# sane_serial.net
KiCad netlist of a schematic drawn in EAGLE
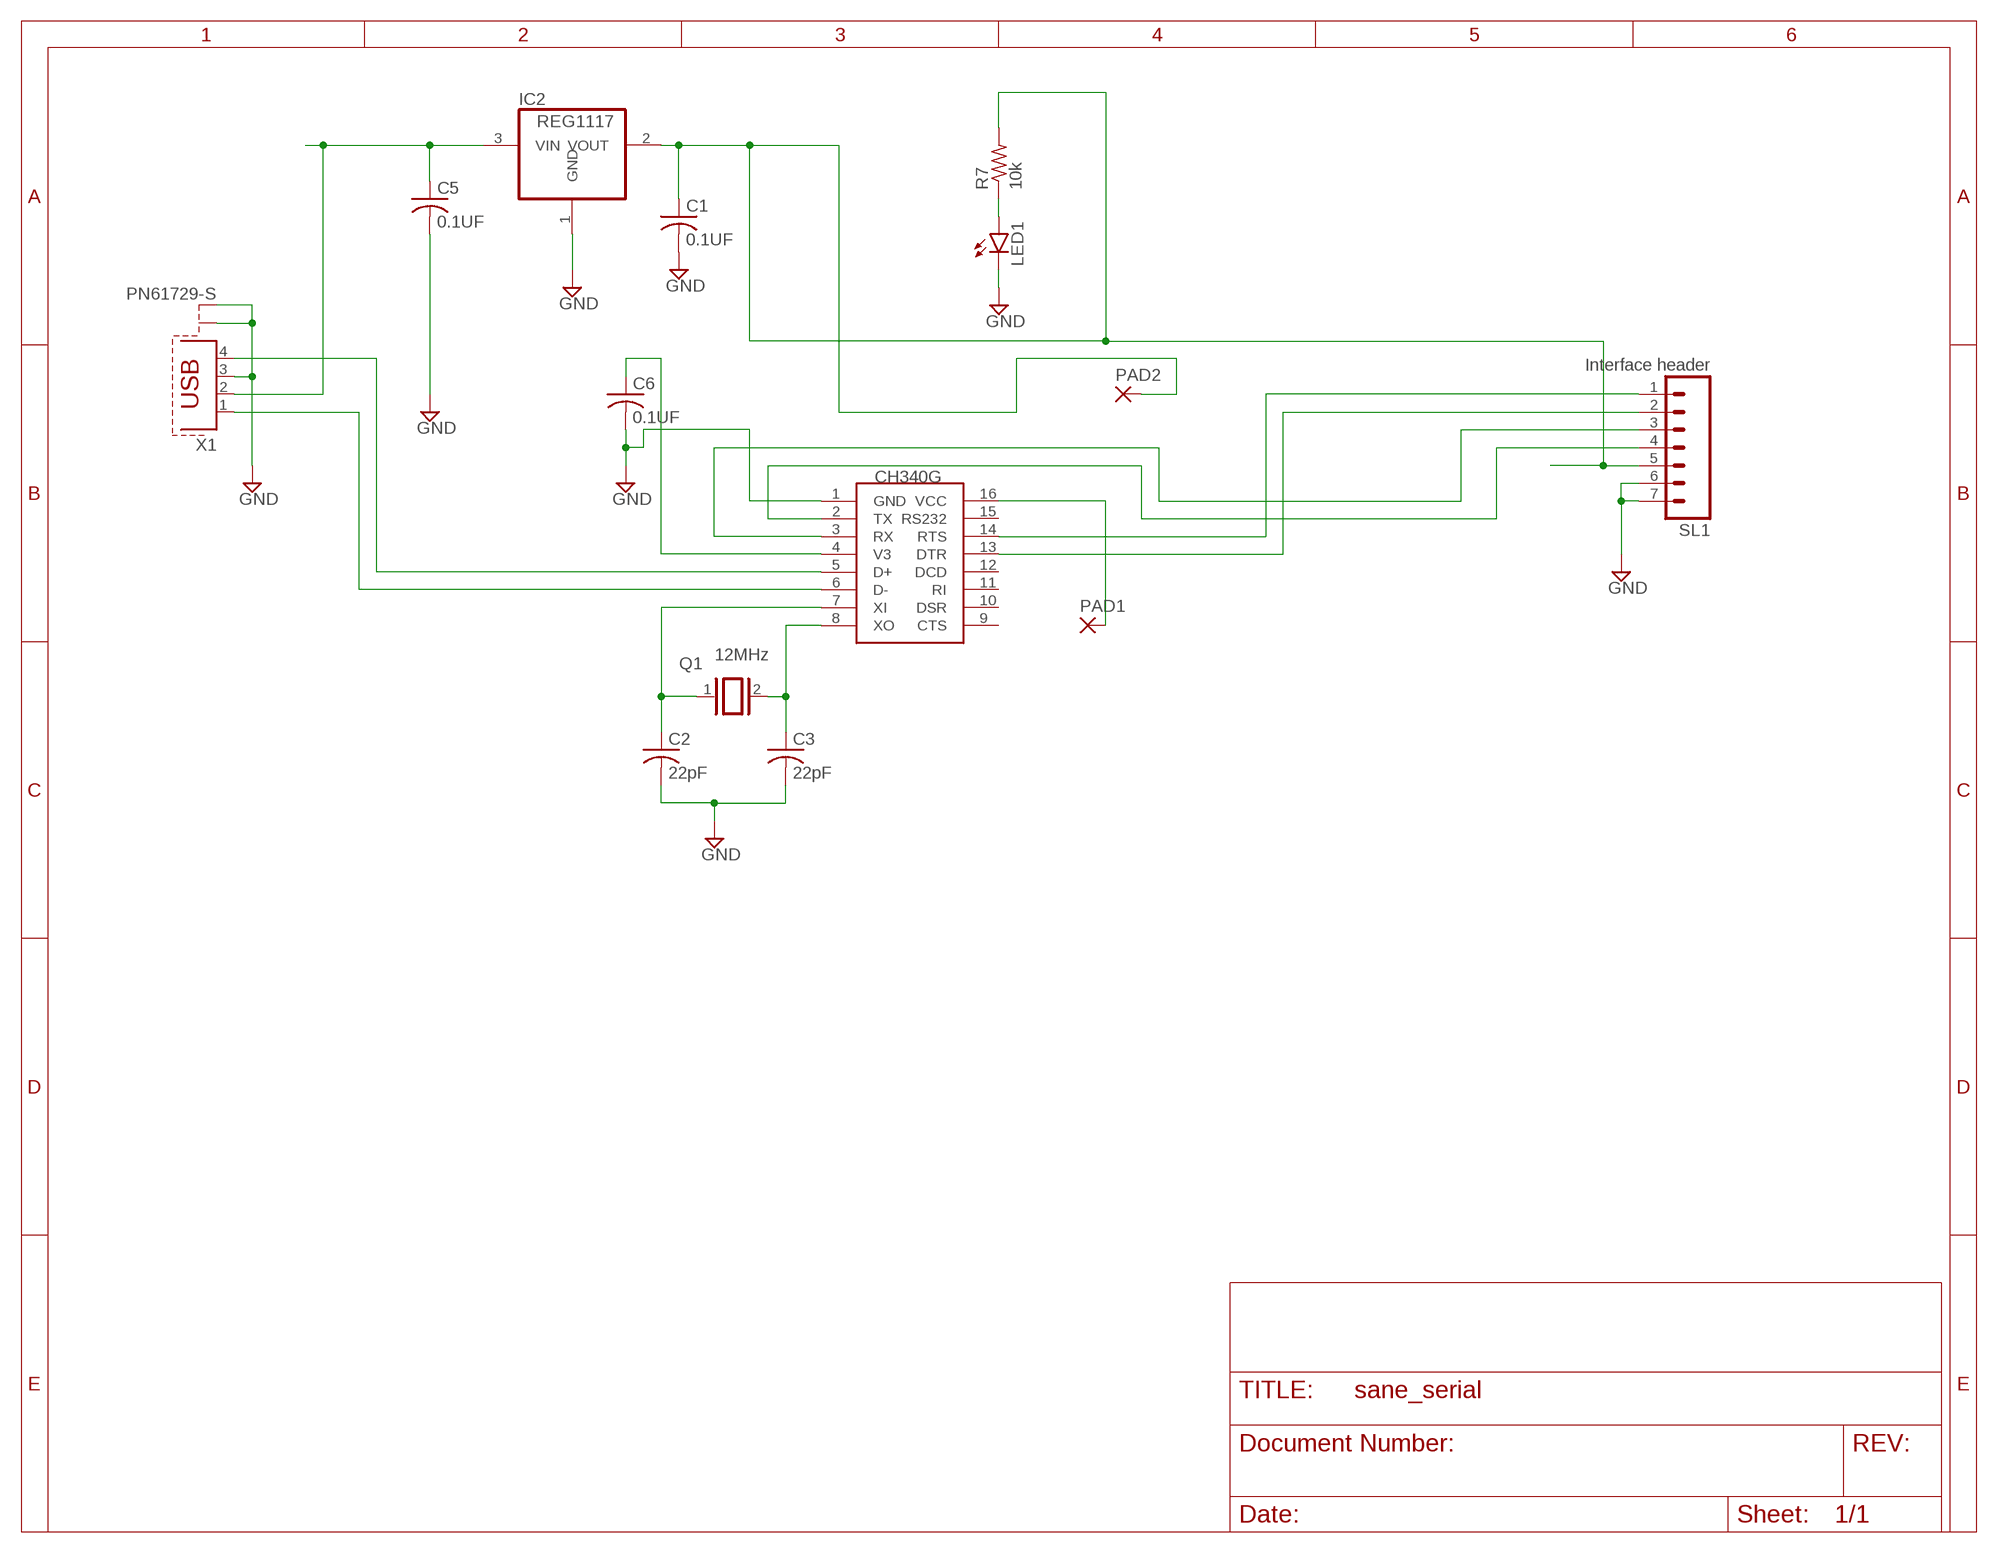
[diagram p0: schematic, sheet 1]

(export (version "E")
  (design (tool "Eeschema 10.0.6"))
  (components
    (comp (ref "C1")
      (value "0.1UF")
      (footprint "eagle-import:C050-024X044")
      (libsource (lib "eagle-import") (part "C-US050-024X044"))
    )
    (comp (ref "C2")
      (value "22pF")
      (footprint "eagle-import:C050-024X044")
      (libsource (lib "eagle-import") (part "C-US050-024X044"))
    )
    (comp (ref "C3")
      (value "22pF")
      (footprint "eagle-import:C050-024X044")
      (libsource (lib "eagle-import") (part "C-US050-024X044"))
    )
    (comp (ref "C5")
      (value "0.1UF")
      (footprint "eagle-import:C050-024X044")
      (libsource (lib "eagle-import") (part "C-US050-024X044"))
    )
    (comp (ref "C6")
      (value "0.1UF")
      (footprint "eagle-import:C050-024X044")
      (libsource (lib "eagle-import") (part "C-US050-024X044"))
    )
    (comp (ref "IC2")
      (value "REG1117")
      (footprint "eagle-import:SOT223")
      (libsource (lib "eagle-import") (part "REG1117"))
    )
    (comp (ref "LED1")
      (value "LED5MM")
      (footprint "eagle-import:LED5MM")
      (libsource (lib "eagle-import") (part "LED5MM"))
    )
    (comp (ref "PAD1")
      (value "1,6/0,9")
      (footprint "eagle-import:1,6_0,9")
      (libsource (lib "eagle-import") (part "1,6/0,9"))
    )
    (comp (ref "PAD2")
      (value "1,6/0,9")
      (footprint "eagle-import:1,6_0,9")
      (libsource (lib "eagle-import") (part "1,6/0,9"))
    )
    (comp (ref "Q1")
      (value "12MHz")
      (footprint "eagle-import:QS")
      (libsource (lib "eagle-import") (part "XTAL/S"))
    )
    (comp (ref "R7")
      (value "10k")
      (footprint "eagle-import:0204_7")
      (libsource (lib "eagle-import") (part "R-US_0204/7"))
    )
    (comp (ref "SL1")
      (value "Interface header")
      (footprint "eagle-import:07P")
      (libsource (lib "eagle-import") (part "M07"))
    )
    (comp (ref "U$1")
      (value "CH340G")
      (footprint "eagle-import:SOIC16")
      (libsource (lib "eagle-import") (part "CH340G"))
    )
    (comp (ref "X1")
      (value "PN61729-S")
      (footprint "eagle-import:PN61729-S")
      (libsource (lib "eagle-import") (part "PN61729-S"))
    )
  )
  (nets
    (net (code "1") (name "GND") (class "Default")
      (node (ref "C1") (pin "2") (pinfunction "2_2") (pintype "passive"))
      (node (ref "C2") (pin "2") (pinfunction "2_2") (pintype "passive"))
      (node (ref "C3") (pin "2") (pinfunction "2_2") (pintype "passive"))
      (node (ref "C5") (pin "2") (pinfunction "2_2") (pintype "passive"))
      (node (ref "C6") (pin "2") (pinfunction "2_2") (pintype "passive"))
      (node (ref "IC2") (pin "1") (pinfunction "GND_1") (pintype "power_in"))
      (node (ref "LED1") (pin "K") (pinfunction "C_K") (pintype "passive"))
      (node (ref "SL1") (pin "6") (pinfunction "6_6") (pintype "passive"))
      (node (ref "SL1") (pin "7") (pinfunction "7_7") (pintype "passive"))
      (node (ref "U$1") (pin "1") (pinfunction "GND_1") (pintype "bidirectional"))
      (node (ref "X1") (pin "3") (pinfunction "3_3") (pintype "passive"))
      (node (ref "X1") (pin "S1") (pinfunction "S1_S1") (pintype "passive"))
      (node (ref "X1") (pin "S2") (pinfunction "S2_S2") (pintype "passive"))
    )
    (net (code "2") (name "Net-(IC2-VIN)") (class "Default")
      (node (ref "C5") (pin "1") (pinfunction "1_1") (pintype "passive"))
      (node (ref "IC2") (pin "3") (pinfunction "VIN_3") (pintype "input"))
      (node (ref "X1") (pin "2") (pinfunction "2_2") (pintype "passive"))
    )
    (net (code "3") (name "Net-(IC2-VOUT)") (class "Default")
      (node (ref "C1") (pin "1") (pinfunction "1_1") (pintype "passive"))
      (node (ref "IC2") (pin "2") (pinfunction "VOUT_2") (pintype "output"))
      (node (ref "PAD2") (pin "1") (pinfunction "P_1") (pintype "passive"))
      (node (ref "R7") (pin "2") (pinfunction "2_2") (pintype "passive"))
      (node (ref "SL1") (pin "5") (pinfunction "5_5") (pintype "passive"))
    )
    (net (code "4") (name "Net-(LED1-PadA)") (class "Default")
      (node (ref "LED1") (pin "A") (pinfunction "A_A") (pintype "passive"))
      (node (ref "R7") (pin "1") (pinfunction "1_1") (pintype "passive"))
    )
    (net (code "5") (name "Net-(PAD1-P)") (class "Default")
      (node (ref "PAD1") (pin "1") (pinfunction "P_1") (pintype "passive"))
      (node (ref "U$1") (pin "16") (pinfunction "VCC_16") (pintype "bidirectional"))
    )
    (net (code "6") (name "Net-(U$1-D+)") (class "Default")
      (node (ref "U$1") (pin "5") (pinfunction "D+_5") (pintype "bidirectional"))
      (node (ref "X1") (pin "4") (pinfunction "4_4") (pintype "passive"))
    )
    (net (code "7") (name "Net-(U$1-D-)") (class "Default")
      (node (ref "U$1") (pin "6") (pinfunction "D-_6") (pintype "bidirectional"))
      (node (ref "X1") (pin "1") (pinfunction "1_1") (pintype "passive"))
    )
    (net (code "8") (name "Net-(U$1-DTR)") (class "Default")
      (node (ref "SL1") (pin "2") (pinfunction "2_2") (pintype "passive"))
      (node (ref "U$1") (pin "13") (pinfunction "DTR_13") (pintype "bidirectional"))
    )
    (net (code "9") (name "Net-(U$1-RTS)") (class "Default")
      (node (ref "SL1") (pin "1") (pinfunction "1_1") (pintype "passive"))
      (node (ref "U$1") (pin "14") (pinfunction "RTS_14") (pintype "bidirectional"))
    )
    (net (code "10") (name "Net-(U$1-RX)") (class "Default")
      (node (ref "SL1") (pin "3") (pinfunction "3_3") (pintype "passive"))
      (node (ref "U$1") (pin "3") (pinfunction "RX_3") (pintype "bidirectional"))
    )
    (net (code "11") (name "Net-(U$1-TX)") (class "Default")
      (node (ref "SL1") (pin "4") (pinfunction "4_4") (pintype "passive"))
      (node (ref "U$1") (pin "2") (pinfunction "TX_2") (pintype "bidirectional"))
    )
    (net (code "12") (name "Net-(U$1-V3)") (class "Default")
      (node (ref "C6") (pin "1") (pinfunction "1_1") (pintype "passive"))
      (node (ref "U$1") (pin "4") (pinfunction "V3_4") (pintype "bidirectional"))
    )
    (net (code "13") (name "Net-(U$1-XI)") (class "Default")
      (node (ref "C2") (pin "1") (pinfunction "1_1") (pintype "passive"))
      (node (ref "Q1") (pin "1") (pinfunction "1_1") (pintype "passive"))
      (node (ref "U$1") (pin "7") (pinfunction "XI_7") (pintype "bidirectional"))
    )
    (net (code "14") (name "Net-(U$1-XO)") (class "Default")
      (node (ref "C3") (pin "1") (pinfunction "1_1") (pintype "passive"))
      (node (ref "Q1") (pin "2") (pinfunction "2_2") (pintype "passive"))
      (node (ref "U$1") (pin "8") (pinfunction "XO_8") (pintype "bidirectional"))
    )
    (net (code "15") (name "unconnected-(U$1-CTS-Pad9)") (class "Default")
      (node (ref "U$1") (pin "9") (pinfunction "CTS_9") (pintype "bidirectional"))
    )
    (net (code "16") (name "unconnected-(U$1-DCD-Pad12)") (class "Default")
      (node (ref "U$1") (pin "12") (pinfunction "DCD_12") (pintype "bidirectional"))
    )
    (net (code "17") (name "unconnected-(U$1-DSR-Pad10)") (class "Default")
      (node (ref "U$1") (pin "10") (pinfunction "DSR_10") (pintype "bidirectional"))
    )
    (net (code "18") (name "unconnected-(U$1-RI-Pad11)") (class "Default")
      (node (ref "U$1") (pin "11") (pinfunction "RI_11") (pintype "bidirectional"))
    )
    (net (code "19") (name "unconnected-(U$1-RS232-Pad15)") (class "Default")
      (node (ref "U$1") (pin "15") (pinfunction "RS232_15") (pintype "bidirectional"))
    )
  )
)
